# Trinkey-MonoSwitch.net
KiCad netlist of a schematic drawn in EAGLE
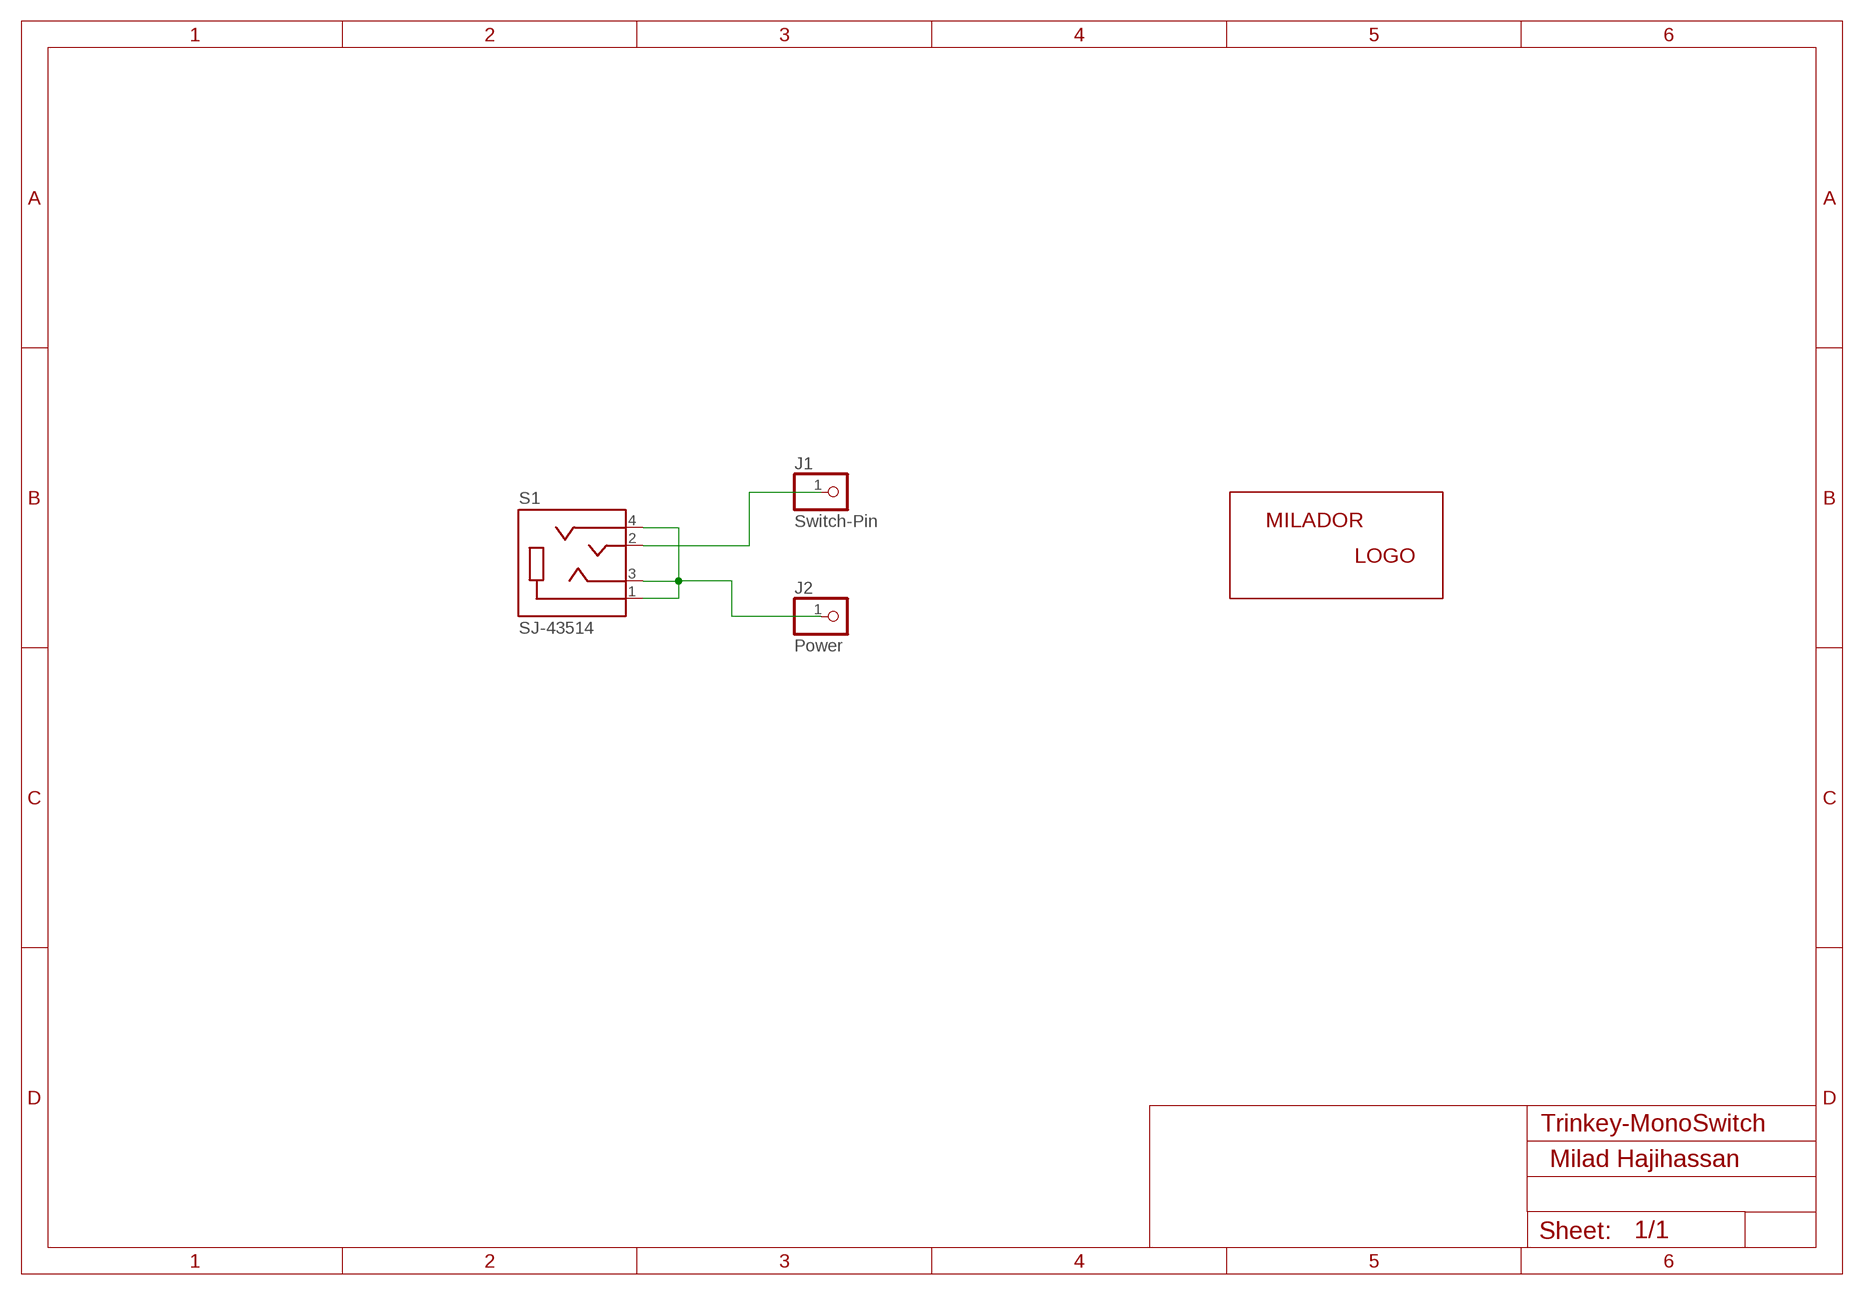
[diagram p0: schematic, sheet 1]

(export (version "E")
  (design (tool "Eeschema 10.0.6"))
  (components
    (comp (ref "J1")
      (value "Switch-Pin")
      (footprint "eagle-import:CASTELLATED_PIN-1X01")
      (libsource (lib "eagle-import") (part "CASTELLATED_PIN-1X01"))
    )
    (comp (ref "J2")
      (value "Power")
      (footprint "eagle-import:CASTELLATED_PIN-1X01")
      (libsource (lib "eagle-import") (part "CASTELLATED_PIN-1X01"))
    )
    (comp (ref "LABEL-LOGO")
      (value "MILADOR-LOGO-SM")
      (footprint "eagle-import:MILADOR_LOGO2")
      (libsource (lib "eagle-import") (part "MILADOR-LOGO-SM"))
    )
    (comp (ref "S1")
      (value "SJ-43514")
      (footprint "eagle-import:CUI_SJ-43514")
      (libsource (lib "eagle-import") (part "SJ-43514"))
    )
  )
  (nets
    (net (code "1") (name "Net-(S1-RING1)") (class "Default")
      (node (ref "J2") (pin "1") (pinfunction "1_1") (pintype "passive"))
      (node (ref "S1") (pin "1") (pinfunction "SLEEVE_1") (pintype "passive"))
      (node (ref "S1") (pin "3") (pinfunction "RING1_3") (pintype "passive"))
      (node (ref "S1") (pin "4") (pinfunction "RING2_4") (pintype "passive"))
    )
    (net (code "2") (name "Net-(S1-TIP)") (class "Default")
      (node (ref "J1") (pin "1") (pinfunction "1_1") (pintype "passive"))
      (node (ref "S1") (pin "2") (pinfunction "TIP_2") (pintype "passive"))
    )
  )
)
